# Sheet1.net
KiCad netlist of a schematic drawn in Altium Designer
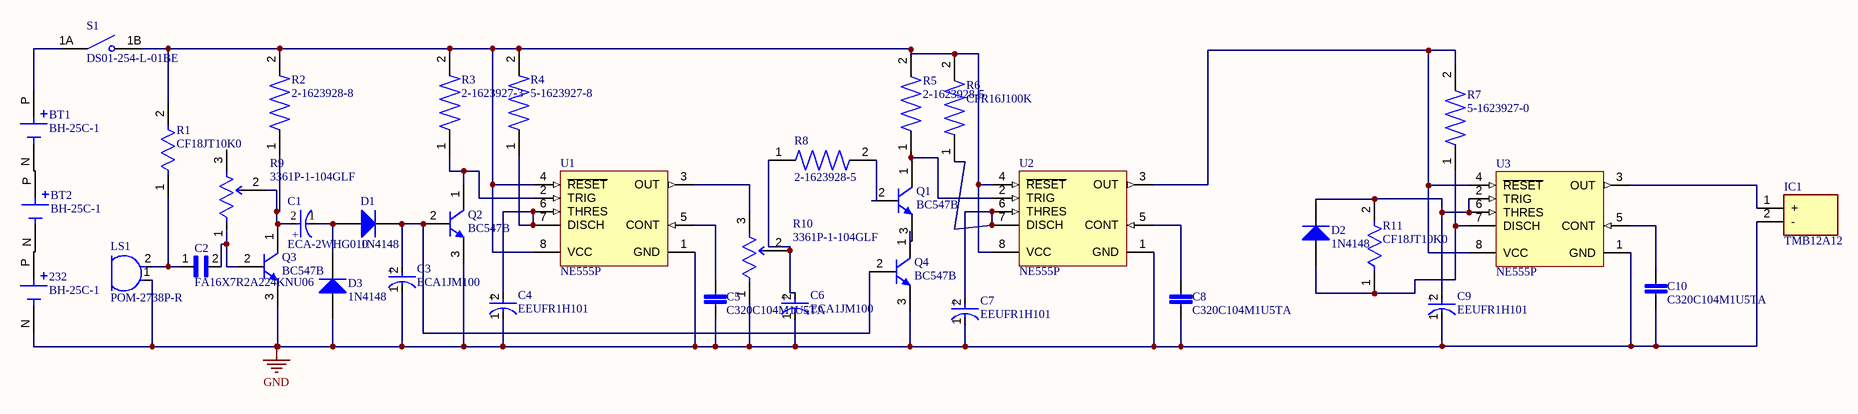
[diagram p0: Sheet1.SchDoc]

(export (version "E")
  (design (tool "Eeschema 10.0.6"))
  (components
    (comp (ref "232")
      (value "BH-25C-1")
      (footprint "BAT_BH-25C-1")
      (description "Battery holder, coin, 20MM 1 CEL PC PIN ¦ Adam Tech BH-25C-1")
      (fields (field (name "MF") "Adam Tech"))
      (libsource (lib "BH-25C-1") (part "BH-25C-1"))
    )
    (comp (ref "BT1")
      (value "BH-25C-1")
      (footprint "BAT_BH-25C-1")
      (description "Battery holder, coin, 20MM 1 CEL PC PIN ¦ Adam Tech BH-25C-1")
      (fields (field (name "MF") "Adam Tech"))
      (libsource (lib "BH-25C-1") (part "BH-25C-1"))
    )
    (comp (ref "BT2")
      (value "BH-25C-1")
      (footprint "BAT_BH-25C-1")
      (description "Battery holder, coin, 20MM 1 CEL PC PIN ¦ Adam Tech BH-25C-1")
      (fields (field (name "MF") "Adam Tech"))
      (libsource (lib "BH-25C-1") (part "BH-25C-1"))
    )
    (comp (ref "C1")
      (value "ECA-2WHG010")
      (footprint "FP-ECA-2WHG010-MFG")
      (description "ECA-2WHG010 Aluminum Electrolytic Capacitor, 1 uF, 450 V, ± 20%, 2000 hours @ 105°C, Radial Leaded")
      (fields (field (name "TOLERANCE") "20%") (field (name "VOLTAGE") "450V"))
      (libsource (lib "Altium Content Vault") (part "a00bbbee19879c290e62620ae7e47b1"))
    )
    (comp (ref "C2")
      (value "FA16X7R2A224KNU06")
      (footprint "CAPRB250W50L550T350H600")
      (description "CAP CER 0.22UF 100V X7R RADIAL")
      (fields (field (name "MF") "TDK"))
      (libsource (lib "FA16X7R2A224KNU06") (part "FA16X7R2A224KNU06"))
    )
    (comp (ref "C3")
      (value "ECA1JM100")
      (footprint "FP-RAD-TH-D_5_0_5-L_11_1-MFG")
      (description "Aluminum Electrolytic Capacitors (Radial Lead Type) 10uF ±20% 63V")
      (fields (field (name "TOLERANCE") "20%") (field (name "VOLTAGE") "63V"))
      (libsource (lib "Altium Content Vault") (part "a00bbbee19879c290e62620ae7e47b1"))
    )
    (comp (ref "C4")
      (value "EEUFR1H101")
      (footprint "FP-RAD-TH-D_8_0_5-L_11_5-MFG")
      (description "Aluminum Electrolytic Capacitors (Radial Lead Type) 100uF ±20% 50V")
      (fields (field (name "VOLTAGE") "50V") (field (name "TOLERANCE") "20%"))
      (libsource (lib "Altium Content Vault") (part "a00bbbee19879c290e62620ae7e47b1"))
    )
    (comp (ref "C5")
      (value "C320C104M1U5TA")
      (footprint "LEADED_DECOUPLING_CAP(.1)")
      (description "0.1ÂµF Â±20% 100V Ceramic Capacitor Z5U Radial")
      (fields (field (name "MF") "KEMET"))
      (libsource (lib "C320C104M1U5TA") (part "C320C104M1U5TA"))
    )
    (comp (ref "C6")
      (value "ECA1JM100")
      (footprint "FP-RAD-TH-D_5_0_5-L_11_1-MFG")
      (description "Aluminum Electrolytic Capacitors (Radial Lead Type) 10uF ±20% 63V")
      (fields (field (name "TOLERANCE") "20%") (field (name "VOLTAGE") "63V"))
      (libsource (lib "Altium Content Vault") (part "a00bbbee19879c290e62620ae7e47b1"))
    )
    (comp (ref "C7")
      (value "EEUFR1H101")
      (footprint "FP-RAD-TH-D_8_0_5-L_11_5-MFG")
      (description "Aluminum Electrolytic Capacitors (Radial Lead Type) 100uF ±20% 50V")
      (fields (field (name "VOLTAGE") "50V") (field (name "TOLERANCE") "20%"))
      (libsource (lib "Altium Content Vault") (part "a00bbbee19879c290e62620ae7e47b1"))
    )
    (comp (ref "C8")
      (value "C320C104M1U5TA")
      (footprint "LEADED_DECOUPLING_CAP(.1)")
      (description "0.1ÂµF Â±20% 100V Ceramic Capacitor Z5U Radial")
      (fields (field (name "MF") "KEMET"))
      (libsource (lib "C320C104M1U5TA") (part "C320C104M1U5TA"))
    )
    (comp (ref "C9")
      (value "EEUFR1H101")
      (footprint "FP-RAD-TH-D_8_0_5-L_11_5-MFG")
      (description "Aluminum Electrolytic Capacitors (Radial Lead Type) 100uF ±20% 50V")
      (fields (field (name "VOLTAGE") "50V") (field (name "TOLERANCE") "20%"))
      (libsource (lib "Altium Content Vault") (part "a00bbbee19879c290e62620ae7e47b1"))
    )
    (comp (ref "C10")
      (value "C320C104M1U5TA")
      (footprint "LEADED_DECOUPLING_CAP(.1)")
      (description "0.1ÂµF Â±20% 100V Ceramic Capacitor Z5U Radial")
      (fields (field (name "MF") "KEMET"))
      (libsource (lib "C320C104M1U5TA") (part "C320C104M1U5TA"))
    )
    (comp (ref "D1")
      (value "1N4148")
      (footprint "NXP-SOD27-2_V")
      (description "High-speed Diode, 100 V, 450 mA, 2-Pin SOD27, RoHS")
      (fields (field (name "MANUFACTURER") "NXP Semiconductors"))
      (libsource (lib "Altium Content Vault") (part "NXP-A1K2-2"))
    )
    (comp (ref "D2")
      (value "1N4148")
      (footprint "NXP-SOD27-2_V")
      (description "High-speed Diode, 100 V, 450 mA, 2-Pin SOD27, RoHS")
      (fields (field (name "MANUFACTURER") "NXP Semiconductors"))
      (libsource (lib "Altium Content Vault") (part "NXP-A1K2-2"))
    )
    (comp (ref "D3")
      (value "1N4148")
      (footprint "NXP-SOD27-2_V")
      (description "High-speed Diode, 100 V, 450 mA, 2-Pin SOD27, RoHS")
      (fields (field (name "MANUFACTURER") "NXP Semiconductors"))
      (libsource (lib "Altium Content Vault") (part "NXP-A1K2-2"))
    )
    (comp (ref "IC1")
      (value "TMB12A12")
      (footprint "SamacSys:TMB12A12")
      (description "Integrated Circuit")
      (libsource (lib "*") (part "TMB12A12"))
    )
    (comp (ref "LS1")
      (value "POM-2738P-R")
      (footprint "FP-POM-2738P-R-MFG")
      (description "MIC COND ANALOG OMNI -38DB")
      (fields
        (field (name "MANUFACTURER") "PUI Audio, Inc.")
        (field (name "OCTOPART") "https://octopart.com/pom-2738p-r-pui+audio-19251807")
      )
      (libsource (lib "Altium Content Vault") (part "b2bcf75ddc372d3ce9fb98e3c3a2780"))
    )
    (comp (ref "Q1")
      (value "BC547B")
      (footprint "Components - 23.01.25 - 09.22:ONSC-TO-92-3-29-11")
      (description "Amplifier Transistor, NPN Silicon, 3-Pin TO-92, Bulk Box")
      (fields (field (name "MANUFACTURER") "On Semiconductor"))
      (libsource (lib "Altium Content Vault") (part "ONSC-NPN-C1B2E3-3"))
    )
    (comp (ref "Q2")
      (value "BC547B")
      (footprint "Components - 23.01.25 - 09.22:ONSC-TO-92-3-29-11")
      (description "Amplifier Transistor, NPN Silicon, 3-Pin TO-92, Bulk Box")
      (fields (field (name "MANUFACTURER") "On Semiconductor"))
      (libsource (lib "Altium Content Vault") (part "ONSC-NPN-C1B2E3-3"))
    )
    (comp (ref "Q3")
      (value "BC547B")
      (footprint "Components - 23.01.25 - 09.22:ONSC-TO-92-3-29-11")
      (description "Amplifier Transistor, NPN Silicon, 3-Pin TO-92, Bulk Box")
      (fields (field (name "MANUFACTURER") "On Semiconductor"))
      (libsource (lib "Altium Content Vault") (part "ONSC-NPN-C1B2E3-3"))
    )
    (comp (ref "Q4")
      (value "BC547B")
      (footprint "ONSC-TO-92-3-29-11")
      (description "Amplifier Transistor, NPN Silicon, 3-Pin TO-92, Bulk Box")
      (fields (field (name "MANUFACTURER") "On Semiconductor"))
      (libsource (lib "Altium Content Vault") (part "ONSC-NPN-C1B2E3-3"))
    )
    (comp (ref "R1")
      (value "CF18JT10K0")
      (footprint "FP-CF18-MFG")
      (description "RES 10K OHM 1/8W 5% CF AXIAL")
      (fields
        (field (name "MANUFACTURER") "Stackpole Electronics")
        (field (name "OCTOPART") "https://octopart.com/cf18jt10k0-stackpole+electronics-19205642")
      )
      (libsource (lib "Altium Content Vault") (part "1029c3af85768c4190bb7ad29bc67b5"))
    )
    (comp (ref "R2")
      (value "2-1623928-8")
      (footprint "RESAD700W45L350D185")
      (description "CFR16 5% 10K")
      (libsource (lib "2-1623928-8") (part "2-1623928-8"))
    )
    (comp (ref "R3")
      (value "2-1623927-3")
      (footprint "RESAD700W45L350D185")
      (description "Carbon Film Resistors - Through Hole 1K Ohm 5% 1/4W Res Carbon Film")
      (fields (field (name "TOLERANCE") "5%") (field (name "MF") "TE Connectivity"))
      (libsource (lib "2-1623927-3") (part "2-1623927-3"))
    )
    (comp (ref "R4")
      (value "5-1623927-8")
      (footprint "RESAD700W45L350D185")
      (description "CFR16 5% 10K")
      (libsource (lib "5-1623927-8") (part "5-1623927-8"))
    )
    (comp (ref "R5")
      (value "2-1623928-5")
      (footprint "RESAD700W45L350D185")
      (description "470 Ohms Â±5% 0.25W, 1/4W Through Hole Resistor Axial - Carbon Film")
      (fields (field (name "TOLERANCE") "5%") (field (name "MF") "TE Connectivity"))
      (libsource (lib "2-1623928-5") (part "2-1623928-5"))
    )
    (comp (ref "R6")
      (value "CFR16J100K")
      (footprint "RESAD700W45L350D185")
      (description "100 kOhms Â±5% 0.25W, 1/4W Through Hole Resistor Axial - Carbon Film")
      (fields (field (name "MF") "TE Connectivity Passive Product"))
      (libsource (lib "CFR16J100K") (part "CFR16J100K"))
    )
    (comp (ref "R7")
      (value "5-1623927-0")
      (footprint "RESAD700W45L350D185")
      (description "CFR16 5% 10K")
      (libsource (lib "5-1623927-0") (part "5-1623927-0"))
    )
    (comp (ref "R8")
      (value "2-1623928-5")
      (footprint "RESAD700W45L350D185")
      (description "470 Ohms Â±5% 0.25W, 1/4W Through Hole Resistor Axial - Carbon Film")
      (fields (field (name "TOLERANCE") "5%") (field (name "MF") "TE Connectivity"))
      (libsource (lib "2-1623928-5") (part "2-1623928-5"))
    )
    (comp (ref "R9")
      (value "3361P-1-104GLF")
      (footprint "FP-3361P-MFG")
      (description "TRIMMER 100K OHM 0.5W GW TOP ADJ")
      (fields (field (name "TOLERANCE") "10%"))
      (libsource (lib "Altium Content Vault") (part "2dcfd2547301a7d3209a5e99acfd772"))
    )
    (comp (ref "R10")
      (value "3361P-1-104GLF")
      (footprint "FP-3361P-MFG")
      (description "TRIMMER 100K OHM 0.5W GW TOP ADJ")
      (fields (field (name "TOLERANCE") "10%"))
      (libsource (lib "Altium Content Vault") (part "2dcfd2547301a7d3209a5e99acfd772"))
    )
    (comp (ref "R11")
      (value "CF18JT10K0")
      (footprint "FP-CF18-MFG")
      (description "RES 10K OHM 1/8W 5% CF AXIAL")
      (fields
        (field (name "MANUFACTURER") "Stackpole Electronics")
        (field (name "OCTOPART") "https://octopart.com/cf18jt10k0-stackpole+electronics-19205642")
      )
      (libsource (lib "Altium Content Vault") (part "1029c3af85768c4190bb7ad29bc67b5"))
    )
    (comp (ref "S1")
      (value "DS01-254-L-01BE")
      (footprint "SW_DS01-254-L-01BE")
      (description "1 Position, Through Hole, 2.54 mm Pitch, Raised Slide Actuator, Flat Bottom, Long Pin, DIP Switch")
      (fields (field (name "MF") "CUI Devices"))
      (libsource (lib "DS01-254-L-01BE") (part "DS01-254-L-01BE"))
    )
    (comp (ref "U1")
      (value "NE555P")
      (footprint "P0008A")
      (description "Precision Timer, 4.5 to 16 V, 0 to 70 degC, 8-Pin DIP, Pb-Free, Tube")
      (fields (field (name "MANUFACTURER") "TexasInstruments"))
      (libsource (lib "Altium Content Vault") (part "TI-NE555-P8"))
    )
    (comp (ref "U2")
      (value "NE555P")
      (footprint "P0008A")
      (description "Precision Timer, 4.5 to 16 V, 0 to 70 degC, 8-Pin DIP, Pb-Free, Tube")
      (fields (field (name "MANUFACTURER") "TexasInstruments"))
      (libsource (lib "Altium Content Vault") (part "TI-NE555-P8"))
    )
    (comp (ref "U3")
      (value "NE555P")
      (footprint "P0008A")
      (description "Precision Timer, 4.5 to 16 V, 0 to 70 degC, 8-Pin DIP, Pb-Free, Tube")
      (fields (field (name "MANUFACTURER") "TexasInstruments"))
      (libsource (lib "Altium Content Vault") (part "TI-NE555-P8"))
    )
  )
  (nets
    (net (code "1") (name "GND") (class "Default")
      (node (ref "232") (pin "N") (pinfunction "N_N") (pintype "passive"))
      (node (ref "C10") (pin "2") (pinfunction "2_2") (pintype "passive"))
      (node (ref "C3") (pin "1") (pinfunction "C_1") (pintype "passive"))
      (node (ref "C4") (pin "1") (pinfunction "C_1") (pintype "passive"))
      (node (ref "C5") (pin "2") (pinfunction "2_2") (pintype "passive"))
      (node (ref "C6") (pin "1") (pinfunction "C_1") (pintype "passive"))
      (node (ref "C7") (pin "1") (pinfunction "C_1") (pintype "passive"))
      (node (ref "C8") (pin "2") (pinfunction "2_2") (pintype "passive"))
      (node (ref "C9") (pin "1") (pinfunction "C_1") (pintype "passive"))
      (node (ref "D3") (pin "1") (pinfunction "A_1") (pintype "passive"))
      (node (ref "IC1") (pin "2") (pinfunction "-_2") (pintype "passive"))
      (node (ref "LS1") (pin "1") (pinfunction "A_1") (pintype "passive"))
      (node (ref "Q2") (pin "3") (pinfunction "E_3") (pintype "passive"))
      (node (ref "Q3") (pin "3") (pinfunction "E_3") (pintype "passive"))
      (node (ref "Q4") (pin "3") (pinfunction "E_3") (pintype "passive"))
      (node (ref "R10") (pin "1") (pinfunction "CCW_1") (pintype "passive"))
      (node (ref "U1") (pin "1") (pinfunction "GND_1") (pintype "power_in"))
      (node (ref "U2") (pin "1") (pinfunction "GND_1") (pintype "power_in"))
      (node (ref "U3") (pin "1") (pinfunction "GND_1") (pintype "power_in"))
    )
    (net (code "2") (name "Net-(232-PadP)") (class "Default")
      (node (ref "232") (pin "P") (pinfunction "P_P") (pintype "passive"))
      (node (ref "BT2") (pin "N") (pinfunction "N_N") (pintype "passive"))
    )
    (net (code "3") (name "Net-(BT1-PadN)") (class "Default")
      (node (ref "BT1") (pin "N") (pinfunction "N_N") (pintype "passive"))
      (node (ref "BT2") (pin "P") (pinfunction "P_P") (pintype "passive"))
    )
    (net (code "4") (name "Net-(C1-A)") (class "Default")
      (node (ref "C1") (pin "2") (pinfunction "A_2") (pintype "passive"))
      (node (ref "Q3") (pin "1") (pinfunction "C_1") (pintype "passive"))
      (node (ref "R2") (pin "1") (pinfunction "1_1") (pintype "passive"))
      (node (ref "R9") (pin "2") (pinfunction "WIPER_2") (pintype "passive"))
    )
    (net (code "5") (name "Net-(C1-C)") (class "Default")
      (node (ref "C1") (pin "1") (pinfunction "C_1") (pintype "passive"))
      (node (ref "D1") (pin "1") (pinfunction "A_1") (pintype "passive"))
      (node (ref "D3") (pin "2") (pinfunction "K_2") (pintype "passive"))
    )
    (net (code "6") (name "Net-(C3-A)") (class "Default")
      (node (ref "C3") (pin "2") (pinfunction "A_2") (pintype "passive"))
      (node (ref "D1") (pin "2") (pinfunction "K_2") (pintype "passive"))
      (node (ref "Q2") (pin "2") (pinfunction "B_2") (pintype "passive"))
      (node (ref "Q4") (pin "2") (pinfunction "B_2") (pintype "passive"))
    )
    (net (code "7") (name "Net-(C4-A)") (class "Default")
      (node (ref "C4") (pin "2") (pinfunction "A_2") (pintype "passive"))
      (node (ref "R4") (pin "1") (pinfunction "1_1") (pintype "passive"))
      (node (ref "U1") (pin "6") (pinfunction "THRES_6") (pintype "input"))
      (node (ref "U1") (pin "7") (pinfunction "DISCH_7") (pintype "open_collector"))
    )
    (net (code "8") (name "Net-(C6-A)") (class "Default")
      (node (ref "C6") (pin "2") (pinfunction "A_2") (pintype "passive"))
      (node (ref "R10") (pin "2") (pinfunction "WIPER_2") (pintype "passive"))
      (node (ref "R8") (pin "1") (pinfunction "1_1") (pintype "passive"))
    )
    (net (code "9") (name "Net-(C7-A)") (class "Default")
      (node (ref "C7") (pin "2") (pinfunction "A_2") (pintype "passive"))
      (node (ref "R6") (pin "1") (pinfunction "1_1") (pintype "passive"))
      (node (ref "U2") (pin "6") (pinfunction "THRES_6") (pintype "input"))
      (node (ref "U2") (pin "7") (pinfunction "DISCH_7") (pintype "open_collector"))
    )
    (net (code "10") (name "Net-(C9-A)") (class "Default")
      (node (ref "C9") (pin "2") (pinfunction "A_2") (pintype "passive"))
      (node (ref "D2") (pin "2") (pinfunction "K_2") (pintype "passive"))
      (node (ref "R11") (pin "2") (pinfunction "2_2") (pintype "passive"))
      (node (ref "U3") (pin "2") (pinfunction "TRIG_2") (pintype "input"))
      (node (ref "U3") (pin "6") (pinfunction "THRES_6") (pintype "input"))
    )
    (net (code "11") (name "Net-(D2-A)") (class "Default")
      (node (ref "D2") (pin "1") (pinfunction "A_1") (pintype "passive"))
      (node (ref "R11") (pin "1") (pinfunction "1_1") (pintype "passive"))
      (node (ref "R7") (pin "1") (pinfunction "1_1") (pintype "passive"))
      (node (ref "U3") (pin "7") (pinfunction "DISCH_7") (pintype "open_collector"))
    )
    (net (code "12") (name "Net-(IC1-+)") (class "Default")
      (node (ref "IC1") (pin "1") (pinfunction "+_1") (pintype "passive"))
      (node (ref "U3") (pin "3") (pinfunction "OUT_3") (pintype "output"))
    )
    (net (code "13") (name "Net-(LS1-C)") (class "Default")
      (node (ref "C2") (pin "1") (pinfunction "1_1") (pintype "passive"))
      (node (ref "LS1") (pin "2") (pinfunction "C_2") (pintype "passive"))
      (node (ref "R1") (pin "1") (pinfunction "1_1") (pintype "passive"))
    )
    (net (code "14") (name "Net-(Q1-B)") (class "Default")
      (node (ref "Q1") (pin "2") (pinfunction "B_2") (pintype "passive"))
      (node (ref "R8") (pin "2") (pinfunction "2_2") (pintype "passive"))
    )
    (net (code "15") (name "Net-(Q1-C)") (class "Default")
      (node (ref "Q1") (pin "1") (pinfunction "C_1") (pintype "passive"))
      (node (ref "R5") (pin "1") (pinfunction "1_1") (pintype "passive"))
      (node (ref "U2") (pin "2") (pinfunction "TRIG_2") (pintype "input"))
    )
    (net (code "16") (name "Net-(Q1-E)") (class "Default")
      (node (ref "Q1") (pin "3") (pinfunction "E_3") (pintype "passive"))
      (node (ref "Q4") (pin "1") (pinfunction "C_1") (pintype "passive"))
    )
    (net (code "17") (name "Net-(Q2-C)") (class "Default")
      (node (ref "Q2") (pin "1") (pinfunction "C_1") (pintype "passive"))
      (node (ref "R3") (pin "1") (pinfunction "1_1") (pintype "passive"))
      (node (ref "U1") (pin "2") (pinfunction "TRIG_2") (pintype "input"))
    )
    (net (code "18") (name "Net-(Q3-B)") (class "Default")
      (node (ref "C2") (pin "2") (pinfunction "2_2") (pintype "passive"))
      (node (ref "Q3") (pin "2") (pinfunction "B_2") (pintype "passive"))
      (node (ref "R9") (pin "1") (pinfunction "CCW_1") (pintype "passive"))
    )
    (net (code "19") (name "Net-(R10-CW)") (class "Default")
      (node (ref "R10") (pin "3") (pinfunction "CW_3") (pintype "passive"))
      (node (ref "U1") (pin "3") (pinfunction "OUT_3") (pintype "output"))
    )
    (net (code "20") (name "Net-(S1-COM1)") (class "Default")
      (node (ref "BT1") (pin "P") (pinfunction "P_P") (pintype "passive"))
      (node (ref "S1") (pin "1A") (pinfunction "COM1_1A") (pintype "passive"))
    )
    (net (code "21") (name "Net-(S1-NO1)") (class "Default")
      (node (ref "R1") (pin "2") (pinfunction "2_2") (pintype "passive"))
      (node (ref "R2") (pin "2") (pinfunction "2_2") (pintype "passive"))
      (node (ref "R3") (pin "2") (pinfunction "2_2") (pintype "passive"))
      (node (ref "R4") (pin "2") (pinfunction "2_2") (pintype "passive"))
      (node (ref "R5") (pin "2") (pinfunction "2_2") (pintype "passive"))
      (node (ref "R6") (pin "2") (pinfunction "2_2") (pintype "passive"))
      (node (ref "S1") (pin "1B") (pinfunction "NO1_1B") (pintype "passive"))
      (node (ref "U1") (pin "4") (pinfunction "~{RESET}_4") (pintype "input"))
      (node (ref "U1") (pin "8") (pinfunction "VCC_8") (pintype "power_in"))
      (node (ref "U2") (pin "4") (pinfunction "~{RESET}_4") (pintype "input"))
      (node (ref "U2") (pin "8") (pinfunction "VCC_8") (pintype "power_in"))
    )
    (net (code "22") (name "Net-(U1-CONT)") (class "Default")
      (node (ref "C5") (pin "1") (pinfunction "1_1") (pintype "passive"))
      (node (ref "U1") (pin "5") (pinfunction "CONT_5") (pintype "input"))
    )
    (net (code "23") (name "Net-(U2-CONT)") (class "Default")
      (node (ref "C8") (pin "1") (pinfunction "1_1") (pintype "passive"))
      (node (ref "U2") (pin "5") (pinfunction "CONT_5") (pintype "input"))
    )
    (net (code "24") (name "Net-(U2-OUT)") (class "Default")
      (node (ref "R7") (pin "2") (pinfunction "2_2") (pintype "passive"))
      (node (ref "U2") (pin "3") (pinfunction "OUT_3") (pintype "output"))
      (node (ref "U3") (pin "4") (pinfunction "~{RESET}_4") (pintype "input"))
      (node (ref "U3") (pin "8") (pinfunction "VCC_8") (pintype "power_in"))
    )
    (net (code "25") (name "Net-(U3-CONT)") (class "Default")
      (node (ref "C10") (pin "1") (pinfunction "1_1") (pintype "passive"))
      (node (ref "U3") (pin "5") (pinfunction "CONT_5") (pintype "input"))
    )
    (net (code "26") (name "unconnected-(R9-CW-Pad3)") (class "Default")
      (node (ref "R9") (pin "3") (pinfunction "CW_3") (pintype "passive"))
    )
  )
)
